# TBD-board.net
KiCad netlist of a schematic drawn in EAGLE
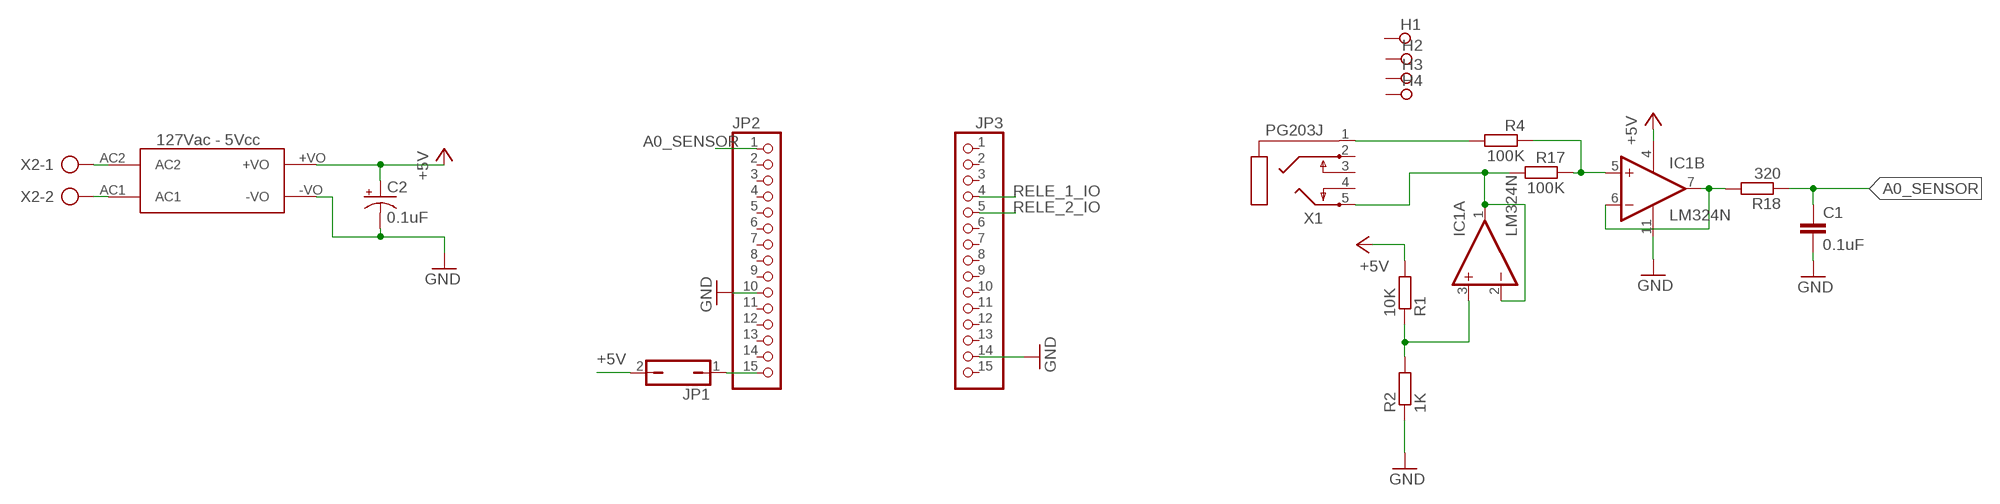
[diagram p0: schematic, sheet 1]

(export (version "E")
  (design (tool "Eeschema 10.0.6"))
  (components
    (comp (ref "C1")
      (value "0.1uF")
      (footprint "eagle-import:C5B5")
      (libsource (lib "eagle-import") (part "C5/5"))
    )
    (comp (ref "C2")
      (value "0.1uF")
      (footprint "eagle-import:E2,5-6")
      (libsource (lib "eagle-import") (part "CPOL-USE2.5-6"))
    )
    (comp (ref "FONTE")
      (value "HLK-PM01")
      (footprint "eagle-import:HLK-PM01")
      (fields (field (name "FONTE") "127Vac - 5Vcc"))
      (libsource (lib "eagle-import") (part "HLK-PM01"))
    )
    (comp (ref "H1")
      (value "SPECIAL_DRILL_0.1000")
      (footprint "eagle-import:PAD_0.1000")
      (libsource (lib "eagle-import") (part "SPECIAL_DRILL_0.1000"))
    )
    (comp (ref "H2")
      (value "SPECIAL_DRILL_0.1000")
      (footprint "eagle-import:PAD_0.1000")
      (libsource (lib "eagle-import") (part "SPECIAL_DRILL_0.1000"))
    )
    (comp (ref "H3")
      (value "SPECIAL_DRILL_0.1000")
      (footprint "eagle-import:PAD_0.1000")
      (libsource (lib "eagle-import") (part "SPECIAL_DRILL_0.1000"))
    )
    (comp (ref "H4")
      (value "SPECIAL_DRILL_0.1000")
      (footprint "eagle-import:PAD_0.1000")
      (libsource (lib "eagle-import") (part "SPECIAL_DRILL_0.1000"))
    )
    (comp (ref "IC1")
      (value "LM324N")
      (footprint "eagle-import:DIL14")
      (libsource (lib "eagle-import") (part "LM324N"))
    )
    (comp (ref "JP1")
      (value "JP1Q")
      (footprint "eagle-import:JP1")
      (libsource (lib "eagle-import") (part "JP1Q"))
    )
    (comp (ref "JP2")
      (value "PINHD-1X15")
      (footprint "eagle-import:1X15")
      (libsource (lib "eagle-import") (part "PINHD-1X15"))
    )
    (comp (ref "JP3")
      (value "PINHD-1X15")
      (footprint "eagle-import:1X15")
      (libsource (lib "eagle-import") (part "PINHD-1X15"))
    )
    (comp (ref "R1")
      (value "10K")
      (footprint "eagle-import:0207_7")
      (libsource (lib "eagle-import") (part "R-EU_0207/7"))
    )
    (comp (ref "R2")
      (value "1K")
      (footprint "eagle-import:0207_7")
      (libsource (lib "eagle-import") (part "R-EU_0207/7"))
    )
    (comp (ref "R4")
      (value "100K")
      (footprint "eagle-import:0207_7")
      (libsource (lib "eagle-import") (part "R-EU_0207/7"))
    )
    (comp (ref "R17")
      (value "100K")
      (footprint "eagle-import:0207_7")
      (libsource (lib "eagle-import") (part "R-EU_0207/7"))
    )
    (comp (ref "R18")
      (value "320")
      (footprint "eagle-import:0207_7")
      (libsource (lib "eagle-import") (part "R-EU_0207/7"))
    )
    (comp (ref "X1")
      (value "PG203J")
      (footprint "eagle-import:PG203J")
      (libsource (lib "eagle-import") (part "PG203J"))
    )
    (comp (ref "X2")
      (value "AK300/2")
      (footprint "eagle-import:AK300_2")
      (libsource (lib "eagle-import") (part "AK300/2"))
    )
  )
  (nets
    (net (code "1") (name "+5V") (class "Default")
      (node (ref "C2") (pin "+") (pinfunction "+_+") (pintype "passive"))
      (node (ref "FONTE") (pin "+VO") (pinfunction "+VO_+VO") (pintype "bidirectional"))
      (node (ref "IC1") (pin "4") (pinfunction "V+_4") (pintype "power_in"))
      (node (ref "JP1") (pin "2") (pinfunction "2_2") (pintype "passive"))
      (node (ref "R1") (pin "2") (pinfunction "2_2") (pintype "passive"))
    )
    (net (code "2") (name "/RELE_1_IO") (class "Default")
      (node (ref "JP3") (pin "4") (pinfunction "4_4") (pintype "passive"))
    )
    (net (code "3") (name "/RELE_2_IO") (class "Default")
      (node (ref "JP3") (pin "5") (pinfunction "5_5") (pintype "passive"))
    )
    (net (code "4") (name "A0_SENSOR") (class "Default")
      (node (ref "C1") (pin "1") (pinfunction "1_1") (pintype "passive"))
      (node (ref "JP2") (pin "1") (pinfunction "1_1") (pintype "passive"))
      (node (ref "R18") (pin "1") (pinfunction "1_1") (pintype "passive"))
    )
    (net (code "5") (name "GND") (class "Default")
      (node (ref "C1") (pin "2") (pinfunction "2_2") (pintype "passive"))
      (node (ref "C2") (pin "-") (pinfunction "-_-") (pintype "passive"))
      (node (ref "FONTE") (pin "-VO") (pinfunction "-VO_-VO") (pintype "bidirectional"))
      (node (ref "IC1") (pin "11") (pinfunction "V-_11") (pintype "power_in"))
      (node (ref "JP2") (pin "10") (pinfunction "10_10") (pintype "passive"))
      (node (ref "JP3") (pin "14") (pinfunction "14_14") (pintype "passive"))
      (node (ref "R2") (pin "1") (pinfunction "1_1") (pintype "passive"))
    )
    (net (code "6") (name "Net-(IC1A-+IN)") (class "Default")
      (node (ref "IC1") (pin "3") (pinfunction "+IN_3") (pintype "input"))
      (node (ref "R1") (pin "1") (pinfunction "1_1") (pintype "passive"))
      (node (ref "R2") (pin "2") (pinfunction "2_2") (pintype "passive"))
    )
    (net (code "7") (name "Net-(IC1A--IN)") (class "Default")
      (node (ref "IC1") (pin "1") (pinfunction "OUT_1") (pintype "output"))
      (node (ref "IC1") (pin "2") (pinfunction "-IN_2") (pintype "input"))
      (node (ref "R17") (pin "2") (pinfunction "2_2") (pintype "passive"))
      (node (ref "X1") (pin "5") (pinfunction "5_5") (pintype "passive"))
    )
    (net (code "8") (name "Net-(IC1B-+IN)") (class "Default")
      (node (ref "IC1") (pin "5") (pinfunction "+IN_5") (pintype "input"))
      (node (ref "R17") (pin "1") (pinfunction "1_1") (pintype "passive"))
      (node (ref "R4") (pin "1") (pinfunction "1_1") (pintype "passive"))
    )
    (net (code "9") (name "Net-(IC1B--IN)") (class "Default")
      (node (ref "IC1") (pin "6") (pinfunction "-IN_6") (pintype "input"))
      (node (ref "IC1") (pin "7") (pinfunction "OUT_7") (pintype "output"))
      (node (ref "R18") (pin "2") (pinfunction "2_2") (pintype "passive"))
    )
    (net (code "10") (name "Net-(JP1-Pad1)") (class "Default")
      (node (ref "JP1") (pin "1") (pinfunction "1_1") (pintype "passive"))
      (node (ref "JP2") (pin "15") (pinfunction "15_15") (pintype "passive"))
    )
    (net (code "11") (name "Net-(R4-Pad2)") (class "Default")
      (node (ref "R4") (pin "2") (pinfunction "2_2") (pintype "passive"))
      (node (ref "X1") (pin "1") (pinfunction "1_1") (pintype "passive"))
    )
    (net (code "12") (name "Net-(X2A-KL)") (class "Default")
      (node (ref "FONTE") (pin "AC2") (pinfunction "AC2_AC2") (pintype "bidirectional"))
      (node (ref "X2") (pin "1") (pinfunction "KL_1") (pintype "passive"))
    )
    (net (code "13") (name "Net-(X2B-KL)") (class "Default")
      (node (ref "FONTE") (pin "AC1") (pinfunction "AC1_AC1") (pintype "bidirectional"))
      (node (ref "X2") (pin "2") (pinfunction "KL_2") (pintype "passive"))
    )
    (net (code "14") (name "unconnected-(H1-Pad1)") (class "Default")
      (node (ref "H1") (pin "1") (pinfunction "1_1") (pintype "passive"))
    )
    (net (code "15") (name "unconnected-(H2-Pad1)") (class "Default")
      (node (ref "H2") (pin "1") (pinfunction "1_1") (pintype "passive"))
    )
    (net (code "16") (name "unconnected-(H3-Pad1)") (class "Default")
      (node (ref "H3") (pin "1") (pinfunction "1_1") (pintype "passive"))
    )
    (net (code "17") (name "unconnected-(H4-Pad1)") (class "Default")
      (node (ref "H4") (pin "1") (pinfunction "1_1") (pintype "passive"))
    )
    (net (code "18") (name "unconnected-(JP2-Pad2)") (class "Default")
      (node (ref "JP2") (pin "2") (pinfunction "2_2") (pintype "passive"))
    )
    (net (code "19") (name "unconnected-(JP2-Pad3)") (class "Default")
      (node (ref "JP2") (pin "3") (pinfunction "3_3") (pintype "passive"))
    )
    (net (code "20") (name "unconnected-(JP2-Pad4)") (class "Default")
      (node (ref "JP2") (pin "4") (pinfunction "4_4") (pintype "passive"))
    )
    (net (code "21") (name "unconnected-(JP2-Pad5)") (class "Default")
      (node (ref "JP2") (pin "5") (pinfunction "5_5") (pintype "passive"))
    )
    (net (code "22") (name "unconnected-(JP2-Pad6)") (class "Default")
      (node (ref "JP2") (pin "6") (pinfunction "6_6") (pintype "passive"))
    )
    (net (code "23") (name "unconnected-(JP2-Pad7)") (class "Default")
      (node (ref "JP2") (pin "7") (pinfunction "7_7") (pintype "passive"))
    )
    (net (code "24") (name "unconnected-(JP2-Pad8)") (class "Default")
      (node (ref "JP2") (pin "8") (pinfunction "8_8") (pintype "passive"))
    )
    (net (code "25") (name "unconnected-(JP2-Pad9)") (class "Default")
      (node (ref "JP2") (pin "9") (pinfunction "9_9") (pintype "passive"))
    )
    (net (code "26") (name "unconnected-(JP2-Pad11)") (class "Default")
      (node (ref "JP2") (pin "11") (pinfunction "11_11") (pintype "passive"))
    )
    (net (code "27") (name "unconnected-(JP2-Pad12)") (class "Default")
      (node (ref "JP2") (pin "12") (pinfunction "12_12") (pintype "passive"))
    )
    (net (code "28") (name "unconnected-(JP2-Pad13)") (class "Default")
      (node (ref "JP2") (pin "13") (pinfunction "13_13") (pintype "passive"))
    )
    (net (code "29") (name "unconnected-(JP2-Pad14)") (class "Default")
      (node (ref "JP2") (pin "14") (pinfunction "14_14") (pintype "passive"))
    )
    (net (code "30") (name "unconnected-(JP3-Pad1)") (class "Default")
      (node (ref "JP3") (pin "1") (pinfunction "1_1") (pintype "passive"))
    )
    (net (code "31") (name "unconnected-(JP3-Pad2)") (class "Default")
      (node (ref "JP3") (pin "2") (pinfunction "2_2") (pintype "passive"))
    )
    (net (code "32") (name "unconnected-(JP3-Pad3)") (class "Default")
      (node (ref "JP3") (pin "3") (pinfunction "3_3") (pintype "passive"))
    )
    (net (code "33") (name "unconnected-(JP3-Pad6)") (class "Default")
      (node (ref "JP3") (pin "6") (pinfunction "6_6") (pintype "passive"))
    )
    (net (code "34") (name "unconnected-(JP3-Pad7)") (class "Default")
      (node (ref "JP3") (pin "7") (pinfunction "7_7") (pintype "passive"))
    )
    (net (code "35") (name "unconnected-(JP3-Pad8)") (class "Default")
      (node (ref "JP3") (pin "8") (pinfunction "8_8") (pintype "passive"))
    )
    (net (code "36") (name "unconnected-(JP3-Pad9)") (class "Default")
      (node (ref "JP3") (pin "9") (pinfunction "9_9") (pintype "passive"))
    )
    (net (code "37") (name "unconnected-(JP3-Pad10)") (class "Default")
      (node (ref "JP3") (pin "10") (pinfunction "10_10") (pintype "passive"))
    )
    (net (code "38") (name "unconnected-(JP3-Pad11)") (class "Default")
      (node (ref "JP3") (pin "11") (pinfunction "11_11") (pintype "passive"))
    )
    (net (code "39") (name "unconnected-(JP3-Pad12)") (class "Default")
      (node (ref "JP3") (pin "12") (pinfunction "12_12") (pintype "passive"))
    )
    (net (code "40") (name "unconnected-(JP3-Pad13)") (class "Default")
      (node (ref "JP3") (pin "13") (pinfunction "13_13") (pintype "passive"))
    )
    (net (code "41") (name "unconnected-(JP3-Pad15)") (class "Default")
      (node (ref "JP3") (pin "15") (pinfunction "15_15") (pintype "passive"))
    )
    (net (code "42") (name "unconnected-(X1-Pad2)") (class "Default")
      (node (ref "X1") (pin "2") (pinfunction "2_2") (pintype "passive"))
    )
    (net (code "43") (name "unconnected-(X1-Pad3)") (class "Default")
      (node (ref "X1") (pin "3") (pinfunction "3_3") (pintype "passive"))
    )
    (net (code "44") (name "unconnected-(X1-Pad4)") (class "Default")
      (node (ref "X1") (pin "4") (pinfunction "4_4") (pintype "passive"))
    )
  )
)
